# Zio_Qwiic_Booster.net
KiCad netlist of a schematic drawn in EAGLE
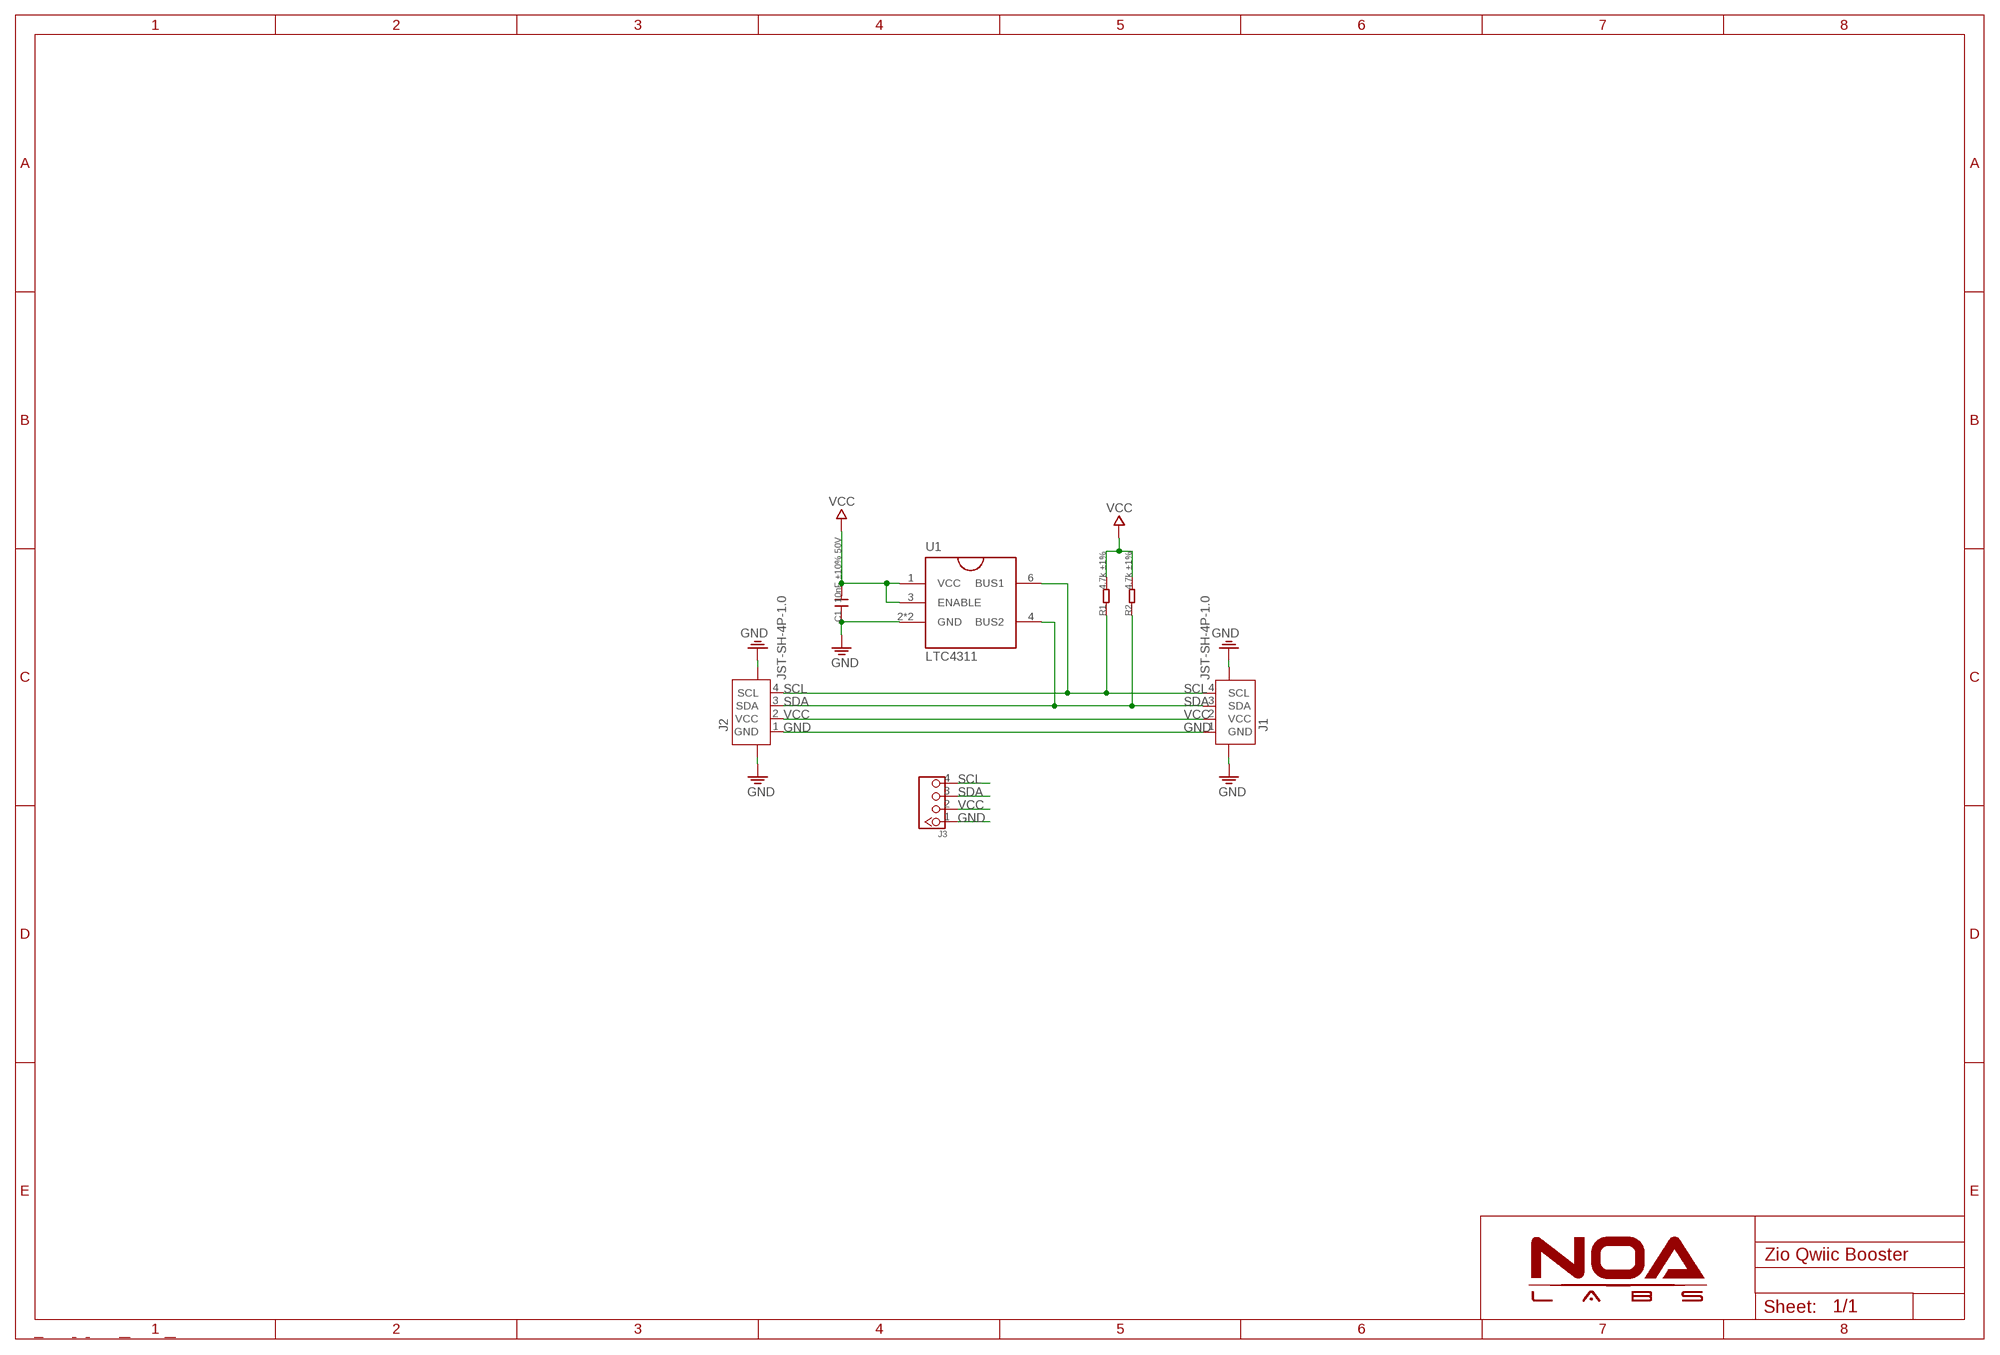
[diagram p0: schematic, sheet 1]

(export (version "E")
  (design (tool "Eeschema 10.0.6"))
  (components
    (comp (ref "C1")
      (value "10nF ±10% 50V")
      (footprint "eagle-import:0603")
      (libsource (lib "eagle-import") (part "C-0603"))
    )
    (comp (ref "J1")
      (value "JST-SH-4P-1.0")
      (footprint "eagle-import:JST-SH-4P")
      (libsource (lib "eagle-import") (part "JST-SH-4P-1.0"))
    )
    (comp (ref "J2")
      (value "JST-SH-4P-1.0")
      (footprint "eagle-import:JST-SH-4P")
      (libsource (lib "eagle-import") (part "JST-SH-4P-1.0"))
    )
    (comp (ref "J3")
      (value "HEADER-4P-60/35MIL")
      (footprint "eagle-import:4P-65_35MIL")
      (libsource (lib "eagle-import") (part "HEADER-4P-60/35MIL"))
    )
    (comp (ref "R1")
      (value "4.7k ±1%")
      (footprint "eagle-import:0603")
      (libsource (lib "eagle-import") (part "R-0603"))
    )
    (comp (ref "R2")
      (value "4.7k ±1%")
      (footprint "eagle-import:0603")
      (libsource (lib "eagle-import") (part "R-0603"))
    )
    (comp (ref "U1")
      (value "LTC4311")
      (footprint "eagle-import:SC70-6L")
      (libsource (lib "eagle-import") (part "LTC4311"))
    )
  )
  (nets
    (net (code "1") (name "/SCL") (class "Default")
      (node (ref "J1") (pin "4") (pinfunction "SCL_4") (pintype "bidirectional"))
      (node (ref "J2") (pin "4") (pinfunction "SCL_4") (pintype "bidirectional"))
      (node (ref "J3") (pin "4") (pinfunction "P$4_4") (pintype "bidirectional"))
      (node (ref "R1") (pin "1") (pinfunction "1_1") (pintype "passive"))
      (node (ref "U1") (pin "6") (pinfunction "BUS1_6") (pintype "bidirectional"))
    )
    (net (code "2") (name "/SDA") (class "Default")
      (node (ref "J1") (pin "3") (pinfunction "SDA_3") (pintype "bidirectional"))
      (node (ref "J2") (pin "3") (pinfunction "SDA_3") (pintype "bidirectional"))
      (node (ref "J3") (pin "3") (pinfunction "P$3_3") (pintype "bidirectional"))
      (node (ref "R2") (pin "1") (pinfunction "1_1") (pintype "passive"))
      (node (ref "U1") (pin "4") (pinfunction "BUS2_4") (pintype "bidirectional"))
    )
    (net (code "3") (name "GND") (class "Default")
      (node (ref "C1") (pin "1") (pinfunction "1_1") (pintype "passive"))
      (node (ref "J1") (pin "1") (pinfunction "GND_1") (pintype "bidirectional"))
      (node (ref "J1") (pin "NC1") (pinfunction "5_NC1") (pintype "bidirectional"))
      (node (ref "J1") (pin "NC2") (pinfunction "6_NC2") (pintype "bidirectional"))
      (node (ref "J2") (pin "1") (pinfunction "GND_1") (pintype "bidirectional"))
      (node (ref "J2") (pin "NC1") (pinfunction "5_NC1") (pintype "bidirectional"))
      (node (ref "J2") (pin "NC2") (pinfunction "6_NC2") (pintype "bidirectional"))
      (node (ref "J3") (pin "1") (pinfunction "P$1_1") (pintype "bidirectional"))
      (node (ref "U1") (pin "2") (pinfunction "GND_2") (pintype "bidirectional"))
      (node (ref "U1") (pin "5") (pinfunction "GND_5") (pintype "bidirectional"))
    )
    (net (code "4") (name "VCC") (class "Default")
      (node (ref "C1") (pin "2") (pinfunction "2_2") (pintype "passive"))
      (node (ref "J1") (pin "2") (pinfunction "VCC_2") (pintype "bidirectional"))
      (node (ref "J2") (pin "2") (pinfunction "VCC_2") (pintype "bidirectional"))
      (node (ref "J3") (pin "2") (pinfunction "P$2_2") (pintype "bidirectional"))
      (node (ref "R1") (pin "2") (pinfunction "2_2") (pintype "passive"))
      (node (ref "R2") (pin "2") (pinfunction "2_2") (pintype "passive"))
      (node (ref "U1") (pin "1") (pinfunction "VCC_1") (pintype "bidirectional"))
      (node (ref "U1") (pin "3") (pinfunction "ENABLE_3") (pintype "bidirectional"))
    )
  )
)
